# board.net
KiCad netlist of a schematic drawn in EAGLE
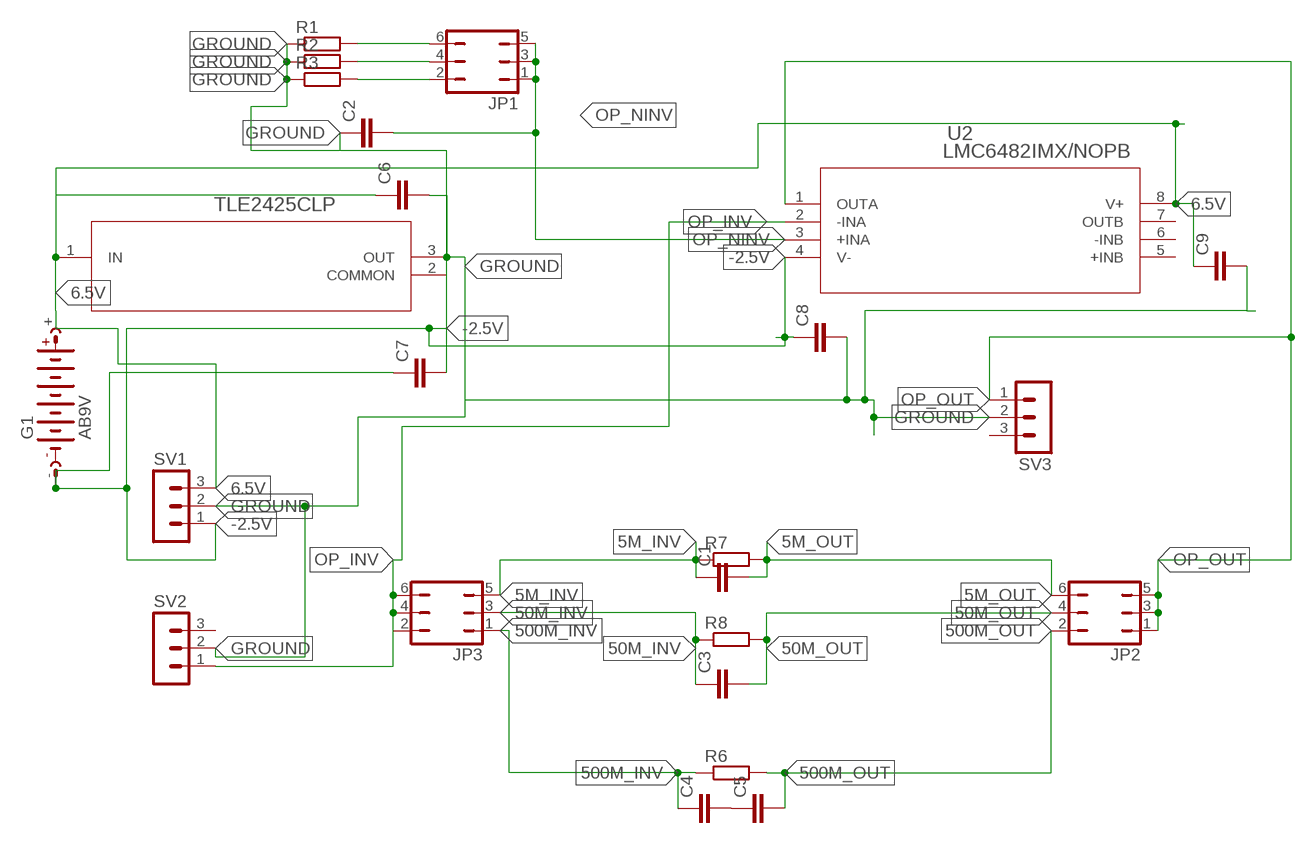
[diagram p0: schematic, sheet 1]

(export (version "E")
  (design (tool "Eeschema 10.0.6"))
  (components
    (comp (ref "C1")
      (value "C-EUC0402")
      (footprint "eagle-import:C0402")
      (libsource (lib "eagle-import") (part "C-EUC0402"))
    )
    (comp (ref "C2")
      (value "C-EUC0805")
      (footprint "eagle-import:C0805")
      (libsource (lib "eagle-import") (part "C-EUC0805"))
    )
    (comp (ref "C3")
      (value "C-EUC0603")
      (footprint "eagle-import:C0603")
      (libsource (lib "eagle-import") (part "C-EUC0603"))
    )
    (comp (ref "C4")
      (value "C-EUC0603")
      (footprint "eagle-import:C0603")
      (libsource (lib "eagle-import") (part "C-EUC0603"))
    )
    (comp (ref "C5")
      (value "C-EUC0805")
      (footprint "eagle-import:C0805")
      (libsource (lib "eagle-import") (part "C-EUC0805"))
    )
    (comp (ref "C6")
      (value "C-EUC0402")
      (footprint "eagle-import:C0402")
      (libsource (lib "eagle-import") (part "C-EUC0402"))
    )
    (comp (ref "C7")
      (value "C-EUC0402")
      (footprint "eagle-import:C0402")
      (libsource (lib "eagle-import") (part "C-EUC0402"))
    )
    (comp (ref "C8")
      (value "C-EUC0402")
      (footprint "eagle-import:C0402")
      (libsource (lib "eagle-import") (part "C-EUC0402"))
    )
    (comp (ref "C9")
      (value "C-EUC0402")
      (footprint "eagle-import:C0402")
      (libsource (lib "eagle-import") (part "C-EUC0402"))
    )
    (comp (ref "G1")
      (value "AB9V")
      (footprint "eagle-import:AB9V")
      (libsource (lib "eagle-import") (part "AB9V"))
    )
    (comp (ref "JP1")
      (value "JP3Q")
      (footprint "eagle-import:JP3Q")
      (libsource (lib "eagle-import") (part "JP3Q"))
    )
    (comp (ref "JP2")
      (value "JP3Q")
      (footprint "eagle-import:JP3Q")
      (libsource (lib "eagle-import") (part "JP3Q"))
    )
    (comp (ref "JP3")
      (value "JP3Q")
      (footprint "eagle-import:JP3Q")
      (libsource (lib "eagle-import") (part "JP3Q"))
    )
    (comp (ref "R1")
      (value "R-EU_R2010")
      (footprint "eagle-import:R2010")
      (libsource (lib "eagle-import") (part "R-EU_R2010"))
    )
    (comp (ref "R2")
      (value "R-EU_R1206")
      (footprint "eagle-import:R1206")
      (libsource (lib "eagle-import") (part "R-EU_R1206"))
    )
    (comp (ref "R3")
      (value "R-EU_R2512")
      (footprint "eagle-import:R2512")
      (libsource (lib "eagle-import") (part "R-EU_R2512"))
    )
    (comp (ref "R6")
      (value "R-EU_R2010")
      (footprint "eagle-import:R2010")
      (libsource (lib "eagle-import") (part "R-EU_R2010"))
    )
    (comp (ref "R7")
      (value "R-EU_R2512")
      (footprint "eagle-import:R2512")
      (libsource (lib "eagle-import") (part "R-EU_R2512"))
    )
    (comp (ref "R8")
      (value "R-EU_R1206")
      (footprint "eagle-import:R1206")
      (libsource (lib "eagle-import") (part "R-EU_R1206"))
    )
    (comp (ref "SV1")
      (value "MA03-1")
      (footprint "eagle-import:MA03-1")
      (libsource (lib "eagle-import") (part "MA03-1"))
    )
    (comp (ref "SV2")
      (value "MA03-1")
      (footprint "eagle-import:MA03-1")
      (libsource (lib "eagle-import") (part "MA03-1"))
    )
    (comp (ref "SV3")
      (value "MA03-1")
      (footprint "eagle-import:MA03-1")
      (libsource (lib "eagle-import") (part "MA03-1"))
    )
    (comp (ref "U1")
      (value "TLE2425CLP")
      (footprint "eagle-import:LP3")
      (libsource (lib "eagle-import") (part "TLE2425CLP"))
    )
    (comp (ref "U2")
      (value "LMC6482IMX/NOPB")
      (footprint "eagle-import:M08A")
      (fields (field (name "MANUFACTURER_PART_NUMBER") "LMC6482IMXNOPB"))
      (libsource (lib "eagle-import") (part "LMC6482IMX/NOPB"))
    )
  )
  (nets
    (net (code "1") (name "-2.5V") (class "Default")
      (node (ref "C7") (pin "1") (pinfunction "1_1") (pintype "passive"))
      (node (ref "C8") (pin "1") (pinfunction "1_1") (pintype "passive"))
      (node (ref "G1") (pin "-") (pinfunction "-_-") (pintype "passive"))
      (node (ref "SV1") (pin "1") (pinfunction "1_1") (pintype "passive"))
      (node (ref "U1") (pin "2") (pinfunction "COMMON_2") (pintype "passive"))
      (node (ref "U2") (pin "4") (pinfunction "V-_4") (pintype "passive"))
    )
    (net (code "2") (name "5M_INV") (class "Default")
      (node (ref "C1") (pin "1") (pinfunction "1_1") (pintype "passive"))
      (node (ref "JP3") (pin "5") (pinfunction "5_5") (pintype "passive"))
      (node (ref "R7") (pin "1") (pinfunction "1_1") (pintype "passive"))
    )
    (net (code "3") (name "5M_OUT") (class "Default")
      (node (ref "C1") (pin "2") (pinfunction "2_2") (pintype "passive"))
      (node (ref "JP2") (pin "6") (pinfunction "6_6") (pintype "passive"))
      (node (ref "R7") (pin "2") (pinfunction "2_2") (pintype "passive"))
    )
    (net (code "4") (name "6.5V") (class "Default")
      (node (ref "C6") (pin "1") (pinfunction "1_1") (pintype "passive"))
      (node (ref "C9") (pin "1") (pinfunction "1_1") (pintype "passive"))
      (node (ref "G1") (pin "+") (pinfunction "+_+") (pintype "passive"))
      (node (ref "SV1") (pin "3") (pinfunction "3_3") (pintype "passive"))
      (node (ref "U1") (pin "1") (pinfunction "IN_1") (pintype "input"))
      (node (ref "U2") (pin "8") (pinfunction "V+_8") (pintype "passive"))
    )
    (net (code "5") (name "50M_INV") (class "Default")
      (node (ref "C3") (pin "1") (pinfunction "1_1") (pintype "passive"))
      (node (ref "JP3") (pin "3") (pinfunction "3_3") (pintype "passive"))
      (node (ref "R8") (pin "1") (pinfunction "1_1") (pintype "passive"))
    )
    (net (code "6") (name "50M_OUT") (class "Default")
      (node (ref "C3") (pin "2") (pinfunction "2_2") (pintype "passive"))
      (node (ref "JP2") (pin "4") (pinfunction "4_4") (pintype "passive"))
      (node (ref "R8") (pin "2") (pinfunction "2_2") (pintype "passive"))
    )
    (net (code "7") (name "500M_INV") (class "Default")
      (node (ref "C4") (pin "1") (pinfunction "1_1") (pintype "passive"))
      (node (ref "JP3") (pin "1") (pinfunction "1_1") (pintype "passive"))
      (node (ref "R6") (pin "1") (pinfunction "1_1") (pintype "passive"))
    )
    (net (code "8") (name "500M_OUT") (class "Default")
      (node (ref "C5") (pin "2") (pinfunction "2_2") (pintype "passive"))
      (node (ref "JP2") (pin "2") (pinfunction "2_2") (pintype "passive"))
      (node (ref "R6") (pin "2") (pinfunction "2_2") (pintype "passive"))
    )
    (net (code "9") (name "GROUND") (class "Default")
      (node (ref "C2") (pin "1") (pinfunction "1_1") (pintype "passive"))
      (node (ref "C6") (pin "2") (pinfunction "2_2") (pintype "passive"))
      (node (ref "C7") (pin "2") (pinfunction "2_2") (pintype "passive"))
      (node (ref "C8") (pin "2") (pinfunction "2_2") (pintype "passive"))
      (node (ref "C9") (pin "2") (pinfunction "2_2") (pintype "passive"))
      (node (ref "R1") (pin "1") (pinfunction "1_1") (pintype "passive"))
      (node (ref "R2") (pin "1") (pinfunction "1_1") (pintype "passive"))
      (node (ref "R3") (pin "1") (pinfunction "1_1") (pintype "passive"))
      (node (ref "SV1") (pin "2") (pinfunction "2_2") (pintype "passive"))
      (node (ref "SV2") (pin "2") (pinfunction "2_2") (pintype "passive"))
      (node (ref "SV3") (pin "2") (pinfunction "2_2") (pintype "passive"))
      (node (ref "U1") (pin "3") (pinfunction "OUT_3") (pintype "output"))
    )
    (net (code "10") (name "Net-(C4-Pad2)") (class "Default")
      (node (ref "C4") (pin "2") (pinfunction "2_2") (pintype "passive"))
      (node (ref "C5") (pin "1") (pinfunction "1_1") (pintype "passive"))
    )
    (net (code "11") (name "Net-(JP1-Pad2)") (class "Default")
      (node (ref "JP1") (pin "2") (pinfunction "2_2") (pintype "passive"))
      (node (ref "R3") (pin "2") (pinfunction "2_2") (pintype "passive"))
    )
    (net (code "12") (name "Net-(JP1-Pad4)") (class "Default")
      (node (ref "JP1") (pin "4") (pinfunction "4_4") (pintype "passive"))
      (node (ref "R2") (pin "2") (pinfunction "2_2") (pintype "passive"))
    )
    (net (code "13") (name "Net-(JP1-Pad6)") (class "Default")
      (node (ref "JP1") (pin "6") (pinfunction "6_6") (pintype "passive"))
      (node (ref "R1") (pin "2") (pinfunction "2_2") (pintype "passive"))
    )
    (net (code "14") (name "OP_INV") (class "Default")
      (node (ref "JP3") (pin "2") (pinfunction "2_2") (pintype "passive"))
      (node (ref "JP3") (pin "4") (pinfunction "4_4") (pintype "passive"))
      (node (ref "JP3") (pin "6") (pinfunction "6_6") (pintype "passive"))
      (node (ref "SV2") (pin "1") (pinfunction "1_1") (pintype "passive"))
      (node (ref "U2") (pin "2") (pinfunction "-INA_2") (pintype "input"))
    )
    (net (code "15") (name "OP_NINV") (class "Default")
      (node (ref "C2") (pin "2") (pinfunction "2_2") (pintype "passive"))
      (node (ref "JP1") (pin "1") (pinfunction "1_1") (pintype "passive"))
      (node (ref "JP1") (pin "3") (pinfunction "3_3") (pintype "passive"))
      (node (ref "JP1") (pin "5") (pinfunction "5_5") (pintype "passive"))
      (node (ref "U2") (pin "3") (pinfunction "+INA_3") (pintype "input"))
    )
    (net (code "16") (name "OP_OUT") (class "Default")
      (node (ref "JP2") (pin "1") (pinfunction "1_1") (pintype "passive"))
      (node (ref "JP2") (pin "3") (pinfunction "3_3") (pintype "passive"))
      (node (ref "JP2") (pin "5") (pinfunction "5_5") (pintype "passive"))
      (node (ref "SV3") (pin "1") (pinfunction "1_1") (pintype "passive"))
      (node (ref "U2") (pin "1") (pinfunction "OUTA_1") (pintype "output"))
    )
    (net (code "17") (name "unconnected-(SV2-Pad3)") (class "Default")
      (node (ref "SV2") (pin "3") (pinfunction "3_3") (pintype "passive"))
    )
    (net (code "18") (name "unconnected-(SV3-Pad3)") (class "Default")
      (node (ref "SV3") (pin "3") (pinfunction "3_3") (pintype "passive"))
    )
    (net (code "19") (name "unconnected-(U2-+INB-Pad5)") (class "Default")
      (node (ref "U2") (pin "5") (pinfunction "+INB_5") (pintype "input"))
    )
    (net (code "20") (name "unconnected-(U2--INB-Pad6)") (class "Default")
      (node (ref "U2") (pin "6") (pinfunction "-INB_6") (pintype "input"))
    )
    (net (code "21") (name "unconnected-(U2-OUTB-Pad7)") (class "Default")
      (node (ref "U2") (pin "7") (pinfunction "OUTB_7") (pintype "output"))
    )
  )
)
